# DDS_Power_Supply.net
KiCad netlist of a schematic drawn in Altium Designer
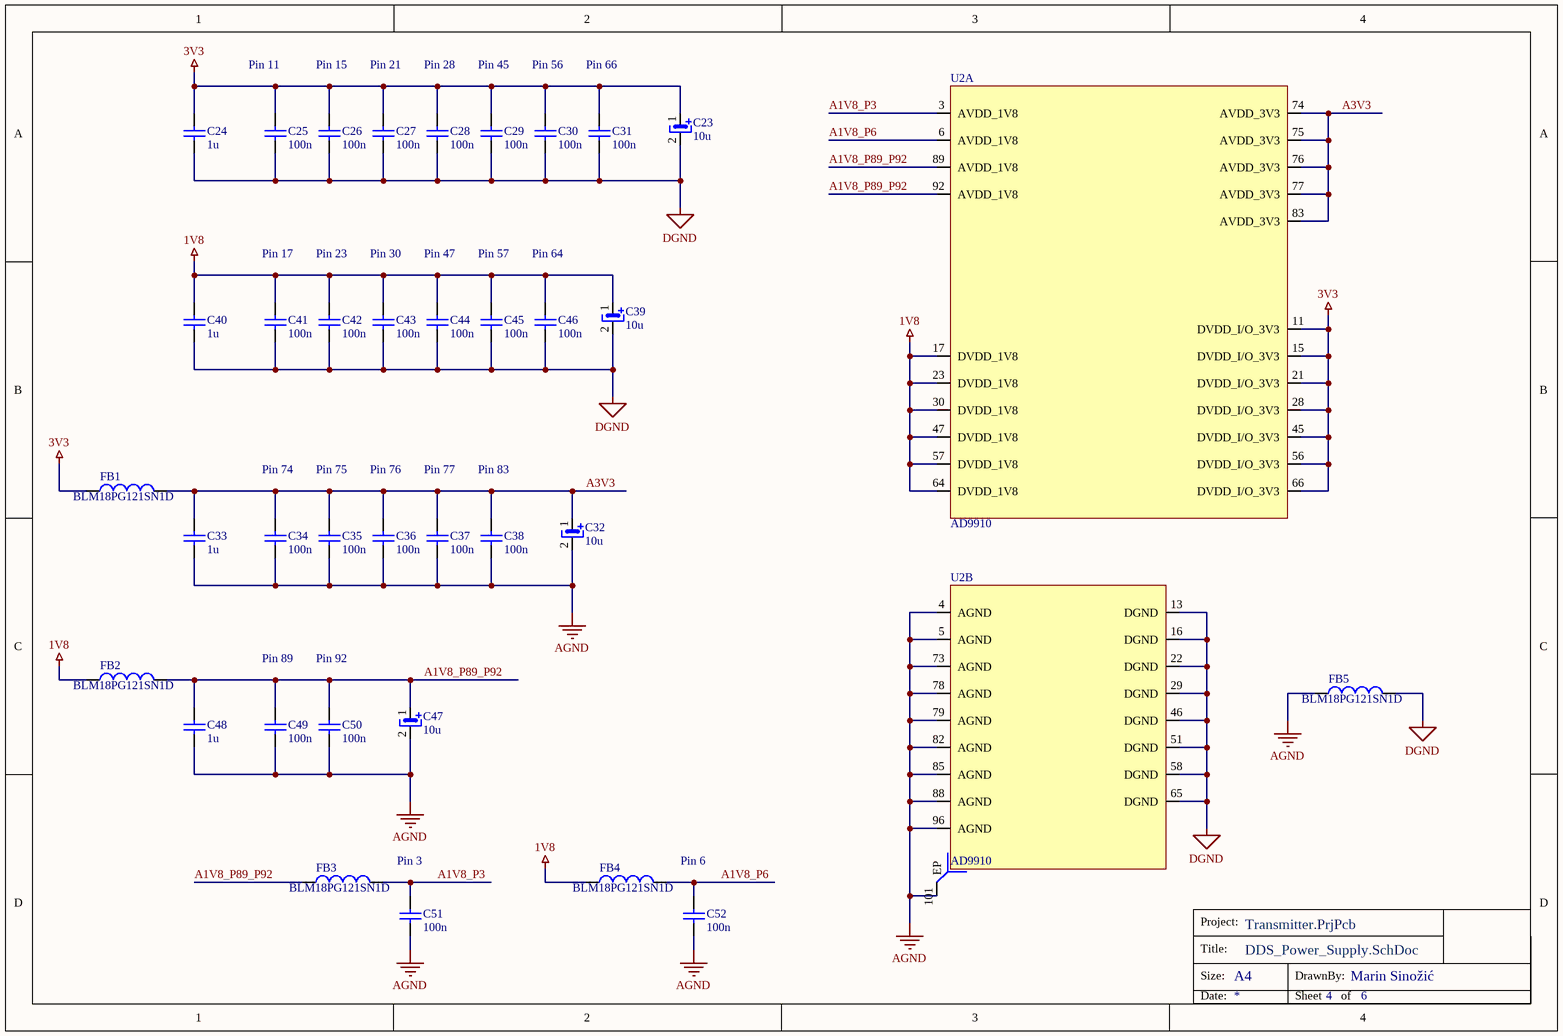
[diagram p0: DDS_Power_Supply.SchDoc]

(export (version "E")
  (design (tool "Eeschema 10.0.6"))
  (components
    (comp (ref "C23")
      (value "10u")
      (footprint "0805")
      (description "CAP TANT 10UF 20% 10V 0805")
      (fields (field (name "MANUFACTURER PART NUMBER") "718-2490-1-ND"))
      (libsource (lib "Tx_board") (part "C_TANT_10uF"))
    )
    (comp (ref "C24")
      (value "1u")
      (footprint "0805")
      (description "CAP CER 1UF 25V X5R 0805")
      (fields (field (name "MANUFACTURER PART NUMBER") "311-1868-1-ND"))
      (libsource (lib "Miscellaneous Devices") (part "Cap"))
    )
    (comp (ref "C25")
      (value "100n")
      (footprint "0603")
      (description "CAP CER 0.1UF 50V X7R 0603")
      (fields (field (name "MANUFACTURER PART NUMBER") "1276-CL10B104KB8WPNDCT-ND"))
      (libsource (lib "Miscellaneous Devices") (part "Cap"))
    )
    (comp (ref "C26")
      (value "100n")
      (footprint "0603")
      (description "CAP CER 0.1UF 50V X7R 0603")
      (fields (field (name "MANUFACTURER PART NUMBER") "1276-CL10B104KB8WPNDCT-ND"))
      (libsource (lib "Miscellaneous Devices") (part "Cap"))
    )
    (comp (ref "C27")
      (value "100n")
      (footprint "0603")
      (description "CAP CER 0.1UF 50V X7R 0603")
      (fields (field (name "MANUFACTURER PART NUMBER") "1276-CL10B104KB8WPNDCT-ND"))
      (libsource (lib "Miscellaneous Devices") (part "Cap"))
    )
    (comp (ref "C28")
      (value "100n")
      (footprint "0603")
      (description "CAP CER 0.1UF 50V X7R 0603")
      (fields (field (name "MANUFACTURER PART NUMBER") "1276-CL10B104KB8WPNDCT-ND"))
      (libsource (lib "Miscellaneous Devices") (part "Cap"))
    )
    (comp (ref "C29")
      (value "100n")
      (footprint "0603")
      (description "CAP CER 0.1UF 50V X7R 0603")
      (fields (field (name "MANUFACTURER PART NUMBER") "1276-CL10B104KB8WPNDCT-ND"))
      (libsource (lib "Miscellaneous Devices") (part "Cap"))
    )
    (comp (ref "C30")
      (value "100n")
      (footprint "0603")
      (description "CAP CER 0.1UF 50V X7R 0603")
      (fields (field (name "MANUFACTURER PART NUMBER") "1276-CL10B104KB8WPNDCT-ND"))
      (libsource (lib "Miscellaneous Devices") (part "Cap"))
    )
    (comp (ref "C31")
      (value "100n")
      (footprint "0603")
      (description "CAP CER 0.1UF 50V X7R 0603")
      (fields (field (name "MANUFACTURER PART NUMBER") "1276-CL10B104KB8WPNDCT-ND"))
      (libsource (lib "Miscellaneous Devices") (part "Cap"))
    )
    (comp (ref "C32")
      (value "10u")
      (footprint "0805")
      (description "CAP TANT 10UF 20% 10V 0805")
      (fields (field (name "MANUFACTURER PART NUMBER") "718-2490-1-ND"))
      (libsource (lib "Tx_board") (part "C_TANT_10uF"))
    )
    (comp (ref "C33")
      (value "1u")
      (footprint "0805")
      (description "CAP CER 1UF 25V X5R 0805")
      (fields (field (name "MANUFACTURER PART NUMBER") "311-1868-1-ND"))
      (libsource (lib "Miscellaneous Devices") (part "Cap"))
    )
    (comp (ref "C34")
      (value "100n")
      (footprint "0603")
      (description "CAP CER 0.1UF 50V X7R 0603")
      (fields (field (name "MANUFACTURER PART NUMBER") "1276-CL10B104KB8WPNDCT-ND"))
      (libsource (lib "Miscellaneous Devices") (part "Cap"))
    )
    (comp (ref "C35")
      (value "100n")
      (footprint "0603")
      (description "CAP CER 0.1UF 50V X7R 0603")
      (fields (field (name "MANUFACTURER PART NUMBER") "1276-CL10B104KB8WPNDCT-ND"))
      (libsource (lib "Miscellaneous Devices") (part "Cap"))
    )
    (comp (ref "C36")
      (value "100n")
      (footprint "0603")
      (description "CAP CER 0.1UF 50V X7R 0603")
      (fields (field (name "MANUFACTURER PART NUMBER") "1276-CL10B104KB8WPNDCT-ND"))
      (libsource (lib "Miscellaneous Devices") (part "Cap"))
    )
    (comp (ref "C37")
      (value "100n")
      (footprint "0603")
      (description "CAP CER 0.1UF 50V X7R 0603")
      (fields (field (name "MANUFACTURER PART NUMBER") "1276-CL10B104KB8WPNDCT-ND"))
      (libsource (lib "Miscellaneous Devices") (part "Cap"))
    )
    (comp (ref "C38")
      (value "100n")
      (footprint "0603")
      (description "CAP CER 0.1UF 50V X7R 0603")
      (fields (field (name "MANUFACTURER PART NUMBER") "1276-CL10B104KB8WPNDCT-ND"))
      (libsource (lib "Miscellaneous Devices") (part "Cap"))
    )
    (comp (ref "C39")
      (value "10u")
      (footprint "0805")
      (description "CAP TANT 10UF 20% 10V 0805")
      (fields (field (name "MANUFACTURER PART NUMBER") "718-2490-1-ND"))
      (libsource (lib "Tx_board") (part "C_TANT_10uF"))
    )
    (comp (ref "C40")
      (value "1u")
      (footprint "0805")
      (description "CAP CER 1UF 25V X5R 0805")
      (fields (field (name "MANUFACTURER PART NUMBER") "311-1868-1-ND"))
      (libsource (lib "Miscellaneous Devices") (part "Cap"))
    )
    (comp (ref "C41")
      (value "100n")
      (footprint "0603")
      (description "CAP CER 0.1UF 50V X7R 0603")
      (fields (field (name "MANUFACTURER PART NUMBER") "1276-CL10B104KB8WPNDCT-ND"))
      (libsource (lib "Miscellaneous Devices") (part "Cap"))
    )
    (comp (ref "C42")
      (value "100n")
      (footprint "0603")
      (description "CAP CER 0.1UF 50V X7R 0603")
      (fields (field (name "MANUFACTURER PART NUMBER") "1276-CL10B104KB8WPNDCT-ND"))
      (libsource (lib "Miscellaneous Devices") (part "Cap"))
    )
    (comp (ref "C43")
      (value "100n")
      (footprint "0603")
      (description "CAP CER 0.1UF 50V X7R 0603")
      (fields (field (name "MANUFACTURER PART NUMBER") "1276-CL10B104KB8WPNDCT-ND"))
      (libsource (lib "Miscellaneous Devices") (part "Cap"))
    )
    (comp (ref "C44")
      (value "100n")
      (footprint "0603")
      (description "CAP CER 0.1UF 50V X7R 0603")
      (fields (field (name "MANUFACTURER PART NUMBER") "1276-CL10B104KB8WPNDCT-ND"))
      (libsource (lib "Miscellaneous Devices") (part "Cap"))
    )
    (comp (ref "C45")
      (value "100n")
      (footprint "0603")
      (description "CAP CER 0.1UF 50V X7R 0603")
      (fields (field (name "MANUFACTURER PART NUMBER") "1276-CL10B104KB8WPNDCT-ND"))
      (libsource (lib "Miscellaneous Devices") (part "Cap"))
    )
    (comp (ref "C46")
      (value "100n")
      (footprint "0603")
      (description "CAP CER 0.1UF 50V X7R 0603")
      (fields (field (name "MANUFACTURER PART NUMBER") "1276-CL10B104KB8WPNDCT-ND"))
      (libsource (lib "Miscellaneous Devices") (part "Cap"))
    )
    (comp (ref "C47")
      (value "10u")
      (footprint "0805")
      (description "CAP TANT 10UF 20% 10V 0805")
      (fields (field (name "MANUFACTURER PART NUMBER") "718-2490-1-ND"))
      (libsource (lib "Tx_board") (part "C_TANT_10uF"))
    )
    (comp (ref "C48")
      (value "1u")
      (footprint "0805")
      (description "CAP CER 1UF 25V X5R 0805")
      (fields (field (name "MANUFACTURER PART NUMBER") "311-1868-1-ND"))
      (libsource (lib "Miscellaneous Devices") (part "Cap"))
    )
    (comp (ref "C49")
      (value "100n")
      (footprint "0603")
      (description "CAP CER 0.1UF 50V X7R 0603")
      (fields (field (name "MANUFACTURER PART NUMBER") "1276-CL10B104KB8WPNDCT-ND"))
      (libsource (lib "Miscellaneous Devices") (part "Cap"))
    )
    (comp (ref "C50")
      (value "100n")
      (footprint "0603")
      (description "CAP CER 0.1UF 50V X7R 0603")
      (fields (field (name "MANUFACTURER PART NUMBER") "1276-CL10B104KB8WPNDCT-ND"))
      (libsource (lib "Miscellaneous Devices") (part "Cap"))
    )
    (comp (ref "C51")
      (value "100n")
      (footprint "0603")
      (description "CAP CER 0.1UF 50V X7R 0603")
      (fields (field (name "MANUFACTURER PART NUMBER") "1276-CL10B104KB8WPNDCT-ND"))
      (libsource (lib "Miscellaneous Devices") (part "Cap"))
    )
    (comp (ref "C52")
      (value "100n")
      (footprint "0603")
      (description "CAP CER 0.1UF 50V X7R 0603")
      (fields (field (name "MANUFACTURER PART NUMBER") "1276-CL10B104KB8WPNDCT-ND"))
      (libsource (lib "Miscellaneous Devices") (part "Cap"))
    )
    (comp (ref "FB1")
      (value "BLM18PG121SN1D")
      (footprint "0603")
      (description "FERRITE BEAD 120 OHM 0603 1LN")
      (fields (field (name "MANUFACTURER PART NUMBER") "490-1037-1-ND"))
      (libsource (lib "Tx_board") (part "FB_0603_120R@100MHz"))
    )
    (comp (ref "FB2")
      (value "BLM18PG121SN1D")
      (footprint "0603")
      (description "FERRITE BEAD 120 OHM 0603 1LN")
      (fields (field (name "MANUFACTURER PART NUMBER") "490-1037-1-ND"))
      (libsource (lib "Tx_board") (part "FB_0603_120R@100MHz"))
    )
    (comp (ref "FB3")
      (value "BLM18PG121SN1D")
      (footprint "0603")
      (description "FERRITE BEAD 120 OHM 0603 1LN")
      (fields (field (name "MANUFACTURER PART NUMBER") "490-1037-1-ND"))
      (libsource (lib "Tx_board") (part "FB_0603_120R@100MHz"))
    )
    (comp (ref "FB4")
      (value "BLM18PG121SN1D")
      (footprint "0603")
      (description "FERRITE BEAD 120 OHM 0603 1LN")
      (fields (field (name "MANUFACTURER PART NUMBER") "490-1037-1-ND"))
      (libsource (lib "Tx_board") (part "FB_0603_120R@100MHz"))
    )
    (comp (ref "FB5")
      (value "BLM18PG121SN1D")
      (footprint "0603")
      (description "FERRITE BEAD 120 OHM 0603 1LN")
      (fields (field (name "MANUFACTURER PART NUMBER") "490-1037-1-ND"))
      (libsource (lib "Tx_board") (part "FB_0603_120R@100MHz"))
    )
    (comp (ref "U2")
      (value "AD9910")
      (footprint "TSQFP50P1600X1600X105_HS-101N")
      (description "ANALOG DEVICES - AD9910BSVZ - Direct Digital Synthesizer, 1 GSPS. 14 Bit, 3.3 V,")
      (fields (field (name "MANUFACTURER PART NUMBER") "505-AD9910BSVZ-ND"))
      (libsource (lib "") (part "AD9910BSVZ_1"))
    )
  )
  (nets
    (net (code "1") (name "/A1V8_P3") (class "Default")
      (node (ref "C51") (pin "2") (pinfunction "2_2") (pintype "passive"))
      (node (ref "FB3") (pin "2") (pinfunction "2_2") (pintype "passive"))
      (node (ref "U2") (pin "3") (pinfunction "AVDD_1V8_3") (pintype "power_in"))
    )
    (net (code "2") (name "/A1V8_P6") (class "Default")
      (node (ref "C52") (pin "2") (pinfunction "2_2") (pintype "passive"))
      (node (ref "FB4") (pin "2") (pinfunction "2_2") (pintype "passive"))
      (node (ref "U2") (pin "6") (pinfunction "AVDD_1V8_6") (pintype "power_in"))
    )
    (net (code "3") (name "/A1V8_P89_P92") (class "Default")
      (node (ref "C47") (pin "1") (pinfunction "+_1") (pintype "passive"))
      (node (ref "C48") (pin "2") (pinfunction "2_2") (pintype "passive"))
      (node (ref "C49") (pin "2") (pinfunction "2_2") (pintype "passive"))
      (node (ref "C50") (pin "2") (pinfunction "2_2") (pintype "passive"))
      (node (ref "FB2") (pin "2") (pinfunction "2_2") (pintype "passive"))
      (node (ref "FB3") (pin "1") (pinfunction "1_1") (pintype "passive"))
      (node (ref "U2") (pin "89") (pinfunction "AVDD_1V8_89") (pintype "power_in"))
      (node (ref "U2") (pin "92") (pinfunction "AVDD_1V8_92") (pintype "power_in"))
    )
    (net (code "4") (name "/A3V3") (class "Default")
      (node (ref "C32") (pin "1") (pinfunction "+_1") (pintype "passive"))
      (node (ref "C33") (pin "2") (pinfunction "2_2") (pintype "passive"))
      (node (ref "C34") (pin "2") (pinfunction "2_2") (pintype "passive"))
      (node (ref "C35") (pin "2") (pinfunction "2_2") (pintype "passive"))
      (node (ref "C36") (pin "2") (pinfunction "2_2") (pintype "passive"))
      (node (ref "C37") (pin "2") (pinfunction "2_2") (pintype "passive"))
      (node (ref "C38") (pin "2") (pinfunction "2_2") (pintype "passive"))
      (node (ref "FB1") (pin "2") (pinfunction "2_2") (pintype "passive"))
      (node (ref "U2") (pin "74") (pinfunction "AVDD_3V3_74") (pintype "power_in"))
      (node (ref "U2") (pin "75") (pinfunction "AVDD_3V3_75") (pintype "power_in"))
      (node (ref "U2") (pin "76") (pinfunction "AVDD_3V3_76") (pintype "power_in"))
      (node (ref "U2") (pin "77") (pinfunction "AVDD_3V3_77") (pintype "power_in"))
      (node (ref "U2") (pin "83") (pinfunction "AVDD_3V3_83") (pintype "power_in"))
    )
    (net (code "5") (name "1V8") (class "Default")
      (node (ref "C39") (pin "1") (pinfunction "+_1") (pintype "passive"))
      (node (ref "C40") (pin "2") (pinfunction "2_2") (pintype "passive"))
      (node (ref "C41") (pin "2") (pinfunction "2_2") (pintype "passive"))
      (node (ref "C42") (pin "2") (pinfunction "2_2") (pintype "passive"))
      (node (ref "C43") (pin "2") (pinfunction "2_2") (pintype "passive"))
      (node (ref "C44") (pin "2") (pinfunction "2_2") (pintype "passive"))
      (node (ref "C45") (pin "2") (pinfunction "2_2") (pintype "passive"))
      (node (ref "C46") (pin "2") (pinfunction "2_2") (pintype "passive"))
      (node (ref "FB2") (pin "1") (pinfunction "1_1") (pintype "passive"))
      (node (ref "FB4") (pin "1") (pinfunction "1_1") (pintype "passive"))
      (node (ref "U2") (pin "17") (pinfunction "DVDD_1V8_17") (pintype "power_in"))
      (node (ref "U2") (pin "23") (pinfunction "DVDD_1V8_23") (pintype "power_in"))
      (node (ref "U2") (pin "30") (pinfunction "DVDD_1V8_30") (pintype "power_in"))
      (node (ref "U2") (pin "47") (pinfunction "DVDD_1V8_47") (pintype "power_in"))
      (node (ref "U2") (pin "57") (pinfunction "DVDD_1V8_57") (pintype "power_in"))
      (node (ref "U2") (pin "64") (pinfunction "DVDD_1V8_64") (pintype "power_in"))
    )
    (net (code "6") (name "3V3") (class "Default")
      (node (ref "C23") (pin "1") (pinfunction "+_1") (pintype "passive"))
      (node (ref "C24") (pin "2") (pinfunction "2_2") (pintype "passive"))
      (node (ref "C25") (pin "2") (pinfunction "2_2") (pintype "passive"))
      (node (ref "C26") (pin "2") (pinfunction "2_2") (pintype "passive"))
      (node (ref "C27") (pin "2") (pinfunction "2_2") (pintype "passive"))
      (node (ref "C28") (pin "2") (pinfunction "2_2") (pintype "passive"))
      (node (ref "C29") (pin "2") (pinfunction "2_2") (pintype "passive"))
      (node (ref "C30") (pin "2") (pinfunction "2_2") (pintype "passive"))
      (node (ref "C31") (pin "2") (pinfunction "2_2") (pintype "passive"))
      (node (ref "FB1") (pin "1") (pinfunction "1_1") (pintype "passive"))
      (node (ref "U2") (pin "11") (pinfunction "DVDD_I/O_3V3_11") (pintype "power_in"))
      (node (ref "U2") (pin "15") (pinfunction "DVDD_I/O_3V3_15") (pintype "power_in"))
      (node (ref "U2") (pin "21") (pinfunction "DVDD_I/O_3V3_21") (pintype "power_in"))
      (node (ref "U2") (pin "28") (pinfunction "DVDD_I/O_3V3_28") (pintype "power_in"))
      (node (ref "U2") (pin "45") (pinfunction "DVDD_I/O_3V3_45") (pintype "power_in"))
      (node (ref "U2") (pin "56") (pinfunction "DVDD_I/O_3V3_56") (pintype "power_in"))
      (node (ref "U2") (pin "66") (pinfunction "DVDD_I/O_3V3_66") (pintype "power_in"))
    )
    (net (code "7") (name "AGND") (class "Default")
      (node (ref "C32") (pin "2") (pinfunction "-_2") (pintype "passive"))
      (node (ref "C33") (pin "1") (pinfunction "1_1") (pintype "passive"))
      (node (ref "C34") (pin "1") (pinfunction "1_1") (pintype "passive"))
      (node (ref "C35") (pin "1") (pinfunction "1_1") (pintype "passive"))
      (node (ref "C36") (pin "1") (pinfunction "1_1") (pintype "passive"))
      (node (ref "C37") (pin "1") (pinfunction "1_1") (pintype "passive"))
      (node (ref "C38") (pin "1") (pinfunction "1_1") (pintype "passive"))
      (node (ref "C47") (pin "2") (pinfunction "-_2") (pintype "passive"))
      (node (ref "C48") (pin "1") (pinfunction "1_1") (pintype "passive"))
      (node (ref "C49") (pin "1") (pinfunction "1_1") (pintype "passive"))
      (node (ref "C50") (pin "1") (pinfunction "1_1") (pintype "passive"))
      (node (ref "C51") (pin "1") (pinfunction "1_1") (pintype "passive"))
      (node (ref "C52") (pin "1") (pinfunction "1_1") (pintype "passive"))
      (node (ref "FB5") (pin "1") (pinfunction "1_1") (pintype "passive"))
      (node (ref "U2") (pin "101") (pinfunction "EP_101") (pintype "power_in"))
      (node (ref "U2") (pin "4") (pinfunction "AGND_4") (pintype "power_in"))
      (node (ref "U2") (pin "5") (pinfunction "AGND_5") (pintype "power_in"))
      (node (ref "U2") (pin "73") (pinfunction "AGND_73") (pintype "power_in"))
      (node (ref "U2") (pin "78") (pinfunction "AGND_78") (pintype "power_in"))
      (node (ref "U2") (pin "79") (pinfunction "AGND_79") (pintype "power_in"))
      (node (ref "U2") (pin "82") (pinfunction "AGND_82") (pintype "power_in"))
      (node (ref "U2") (pin "85") (pinfunction "AGND_85") (pintype "power_in"))
      (node (ref "U2") (pin "88") (pinfunction "AGND_88") (pintype "power_in"))
      (node (ref "U2") (pin "96") (pinfunction "AGND_96") (pintype "power_in"))
    )
    (net (code "8") (name "DGND") (class "Default")
      (node (ref "C23") (pin "2") (pinfunction "-_2") (pintype "passive"))
      (node (ref "C24") (pin "1") (pinfunction "1_1") (pintype "passive"))
      (node (ref "C25") (pin "1") (pinfunction "1_1") (pintype "passive"))
      (node (ref "C26") (pin "1") (pinfunction "1_1") (pintype "passive"))
      (node (ref "C27") (pin "1") (pinfunction "1_1") (pintype "passive"))
      (node (ref "C28") (pin "1") (pinfunction "1_1") (pintype "passive"))
      (node (ref "C29") (pin "1") (pinfunction "1_1") (pintype "passive"))
      (node (ref "C30") (pin "1") (pinfunction "1_1") (pintype "passive"))
      (node (ref "C31") (pin "1") (pinfunction "1_1") (pintype "passive"))
      (node (ref "C39") (pin "2") (pinfunction "-_2") (pintype "passive"))
      (node (ref "C40") (pin "1") (pinfunction "1_1") (pintype "passive"))
      (node (ref "C41") (pin "1") (pinfunction "1_1") (pintype "passive"))
      (node (ref "C42") (pin "1") (pinfunction "1_1") (pintype "passive"))
      (node (ref "C43") (pin "1") (pinfunction "1_1") (pintype "passive"))
      (node (ref "C44") (pin "1") (pinfunction "1_1") (pintype "passive"))
      (node (ref "C45") (pin "1") (pinfunction "1_1") (pintype "passive"))
      (node (ref "C46") (pin "1") (pinfunction "1_1") (pintype "passive"))
      (node (ref "FB5") (pin "2") (pinfunction "2_2") (pintype "passive"))
      (node (ref "U2") (pin "13") (pinfunction "DGND_13") (pintype "power_in"))
      (node (ref "U2") (pin "16") (pinfunction "DGND_16") (pintype "power_in"))
      (node (ref "U2") (pin "22") (pinfunction "DGND_22") (pintype "power_in"))
      (node (ref "U2") (pin "29") (pinfunction "DGND_29") (pintype "power_in"))
      (node (ref "U2") (pin "46") (pinfunction "DGND_46") (pintype "power_in"))
      (node (ref "U2") (pin "51") (pinfunction "DGND_51") (pintype "power_in"))
      (node (ref "U2") (pin "58") (pinfunction "DGND_58") (pintype "power_in"))
      (node (ref "U2") (pin "65") (pinfunction "DGND_65") (pintype "power_in"))
    )
  )
)
